# CNEPuckRevG_Drivers_2.net
KiCad netlist of a schematic drawn in Altium Designer
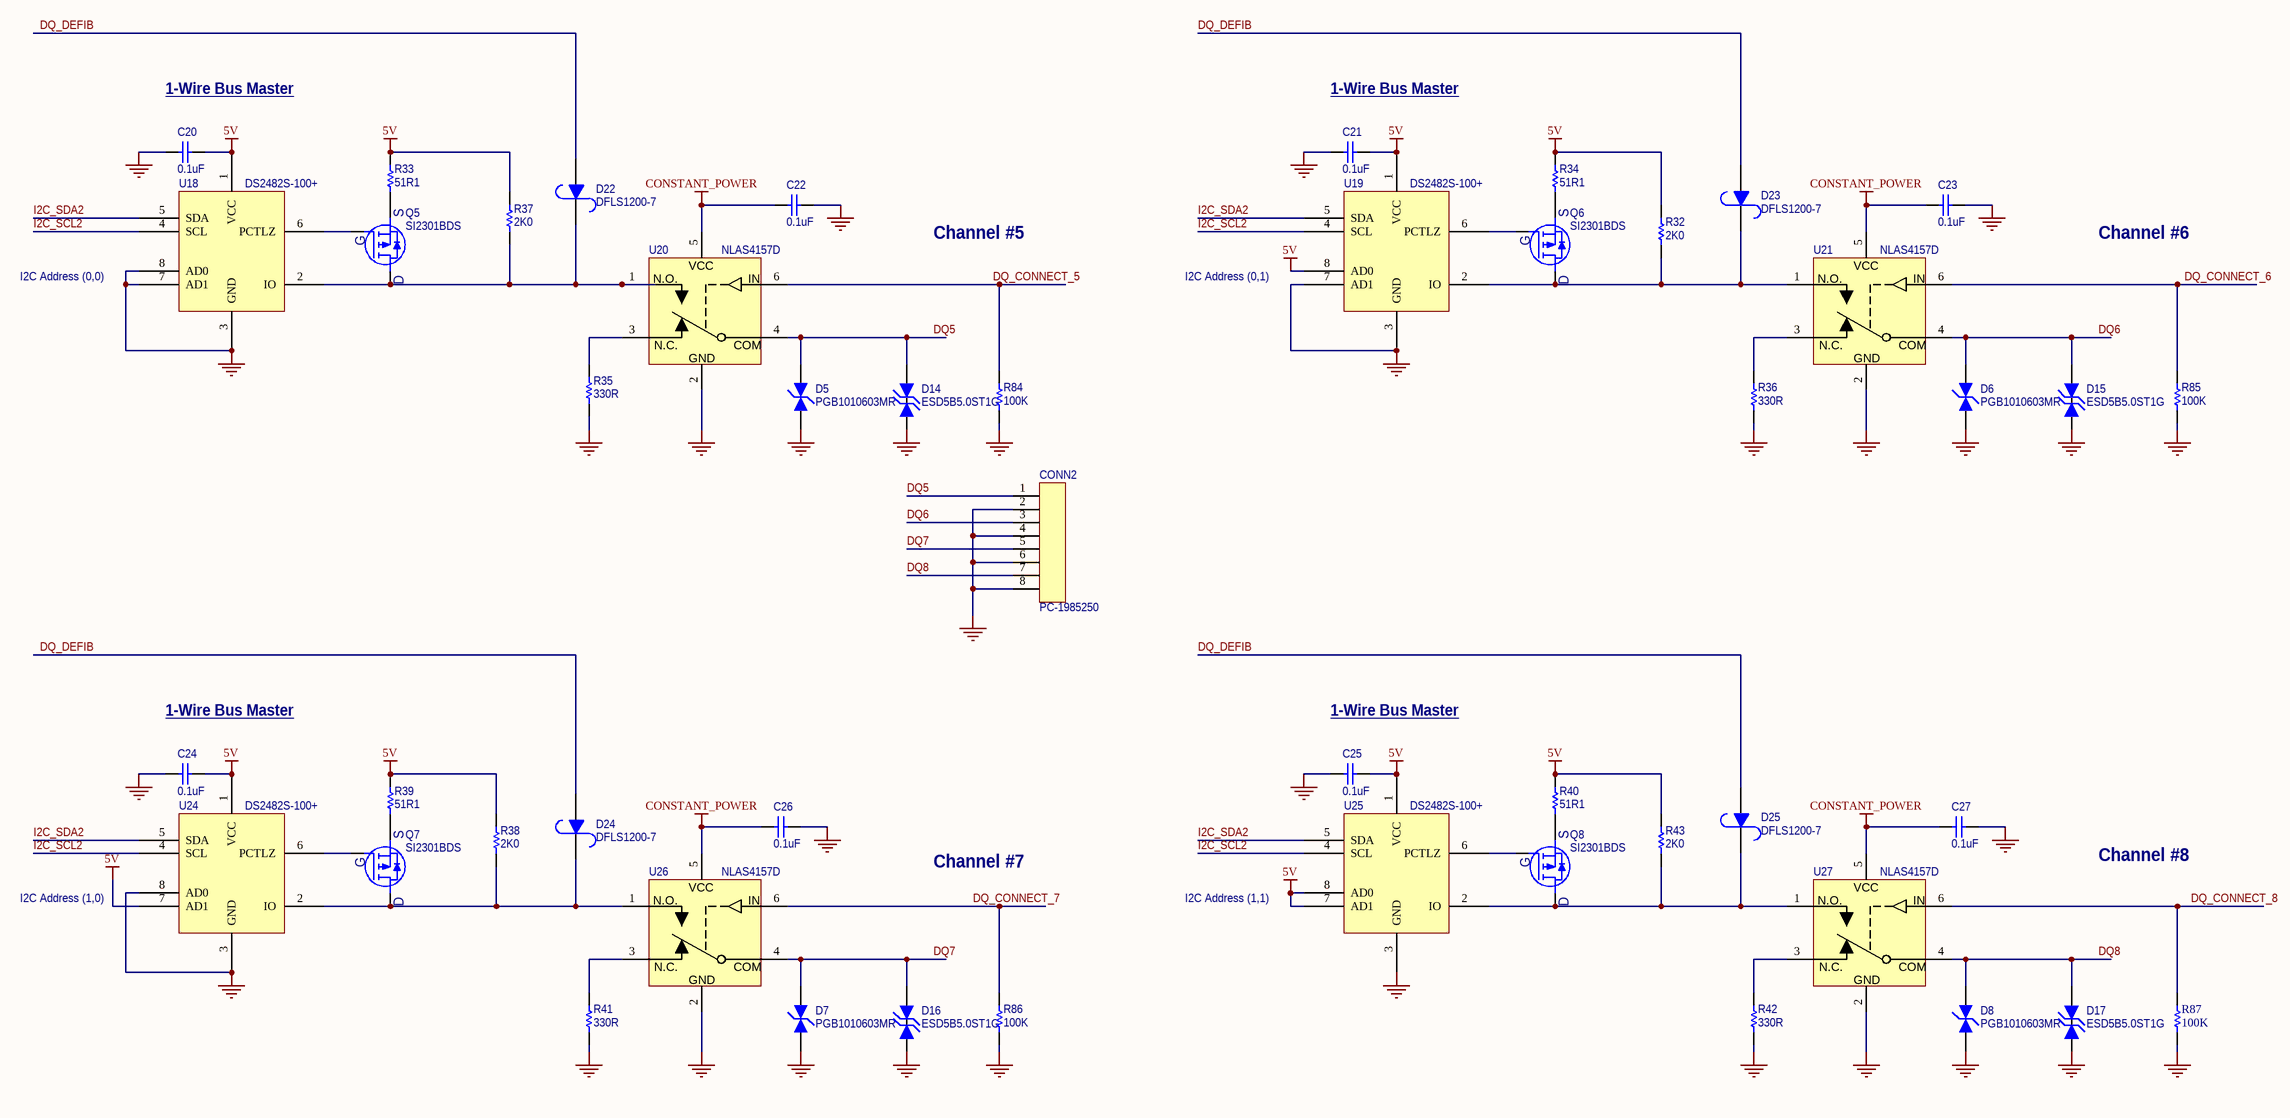
[diagram p0: CNEPuckRevG_Drivers_2.SchDoc]

(export (version "E")
  (design (tool "Eeschema 10.0.6"))
  (components
    (comp (ref "C20")
      (value "0.1uF")
      (footprint "RC0603")
      (description "CAP CERM .1UF 10% 16V X7R 0603")
      (fields (field (name "TOLERANCE") "±10%") (field (name "MANUFACTURER PART NUMBER") "0603YC104KAT2A"))
      (libsource (lib "Swage") (part "0603YC104KAT2A"))
    )
    (comp (ref "C21")
      (value "0.1uF")
      (footprint "RC0603")
      (description "CAP CERM .1UF 10% 16V X7R 0603")
      (fields (field (name "TOLERANCE") "±10%") (field (name "MANUFACTURER PART NUMBER") "0603YC104KAT2A"))
      (libsource (lib "Swage") (part "0603YC104KAT2A"))
    )
    (comp (ref "C22")
      (value "0.1uF")
      (footprint "RC0603")
      (description "CAP CERM .1UF 10% 16V X7R 0603")
      (fields (field (name "TOLERANCE") "±10%") (field (name "MANUFACTURER PART NUMBER") "0603YC104KAT2A"))
      (libsource (lib "Swage") (part "0603YC104KAT2A"))
    )
    (comp (ref "C23")
      (value "0.1uF")
      (footprint "RC0603")
      (description "CAP CERM .1UF 10% 16V X7R 0603")
      (fields (field (name "TOLERANCE") "±10%") (field (name "MANUFACTURER PART NUMBER") "0603YC104KAT2A"))
      (libsource (lib "Swage") (part "0603YC104KAT2A"))
    )
    (comp (ref "C24")
      (value "0.1uF")
      (footprint "RC0603")
      (description "CAP CERM .1UF 10% 16V X7R 0603")
      (fields (field (name "TOLERANCE") "±10%") (field (name "MANUFACTURER PART NUMBER") "0603YC104KAT2A"))
      (libsource (lib "Swage") (part "0603YC104KAT2A"))
    )
    (comp (ref "C25")
      (value "0.1uF")
      (footprint "RC0603")
      (description "CAP CERM .1UF 10% 16V X7R 0603")
      (fields (field (name "TOLERANCE") "±10%") (field (name "MANUFACTURER PART NUMBER") "0603YC104KAT2A"))
      (libsource (lib "Swage") (part "0603YC104KAT2A"))
    )
    (comp (ref "C26")
      (value "0.1uF")
      (footprint "RC0603")
      (description "CAP CERM .1UF 10% 16V X7R 0603")
      (fields (field (name "TOLERANCE") "±10%") (field (name "MANUFACTURER PART NUMBER") "0603YC104KAT2A"))
      (libsource (lib "Swage") (part "0603YC104KAT2A"))
    )
    (comp (ref "C27")
      (value "0.1uF")
      (footprint "RC0603")
      (description "CAP CERM .1UF 10% 16V X7R 0603")
      (fields (field (name "TOLERANCE") "±10%") (field (name "MANUFACTURER PART NUMBER") "0603YC104KAT2A"))
      (libsource (lib "Swage") (part "0603YC104KAT2A"))
    )
    (comp (ref "CONN2")
      (value "PC-1985250")
      (footprint "PTSA1.5/8-3.5-Z")
      (description "TERM BLOCK PCB 8POS 3.5MM GREEN")
      (fields
        (field (name "MANUFACTURER") "Phoenix Contact")
        (field (name "MANUFACTURER PART NUMBER") "1985250")
      )
      (libsource (lib "Swage") (part "1985250"))
    )
    (comp (ref "D5")
      (value "PGB1010603MR")
      (footprint "RC0603")
      (description "SUPPRESSOR ESD 24VDC 0603 SMD")
      (fields (field (name "MANUFACTURER") "Littelfuse Inc"))
      (libsource (lib "Swage") (part "PGB1010603MR"))
    )
    (comp (ref "D6")
      (value "PGB1010603MR")
      (footprint "RC0603")
      (description "SUPPRESSOR ESD 24VDC 0603 SMD")
      (fields (field (name "MANUFACTURER") "Littelfuse Inc"))
      (libsource (lib "Swage") (part "PGB1010603MR"))
    )
    (comp (ref "D7")
      (value "PGB1010603MR")
      (footprint "RC0603")
      (description "SUPPRESSOR ESD 24VDC 0603 SMD")
      (fields (field (name "MANUFACTURER") "Littelfuse Inc"))
      (libsource (lib "Swage") (part "PGB1010603MR"))
    )
    (comp (ref "D8")
      (value "PGB1010603MR")
      (footprint "RC0603")
      (description "SUPPRESSOR ESD 24VDC 0603 SMD")
      (fields (field (name "MANUFACTURER") "Littelfuse Inc"))
      (libsource (lib "Swage") (part "PGB1010603MR"))
    )
    (comp (ref "D14")
      (value "ESD5B5.0ST1G")
      (footprint "SOD-523")
      (description "TVS BIDIRECT 50W SOD523")
      (fields (field (name "MANUFACTURER") "ON Semiconductor"))
      (libsource (lib "Swage") (part "ESD5B5.0ST1G"))
    )
    (comp (ref "D15")
      (value "ESD5B5.0ST1G")
      (footprint "SOD-523")
      (description "TVS BIDIRECT 50W SOD523")
      (fields (field (name "MANUFACTURER") "ON Semiconductor"))
      (libsource (lib "Swage") (part "ESD5B5.0ST1G"))
    )
    (comp (ref "D16")
      (value "ESD5B5.0ST1G")
      (footprint "SOD-523")
      (description "TVS BIDIRECT 50W SOD523")
      (fields (field (name "MANUFACTURER") "ON Semiconductor"))
      (libsource (lib "Swage") (part "ESD5B5.0ST1G"))
    )
    (comp (ref "D17")
      (value "ESD5B5.0ST1G")
      (footprint "SOD-523")
      (description "TVS BIDIRECT 50W SOD523")
      (fields (field (name "MANUFACTURER") "ON Semiconductor"))
      (libsource (lib "Swage") (part "ESD5B5.0ST1G"))
    )
    (comp (ref "D22")
      (value "DFLS1200-7")
      (footprint "POWERDI-123")
      (description "DIODE SCHOTTKY 1A 200V PWRDI 123")
      (fields (field (name "MANUFACTURER") "Diodes Inc"))
      (libsource (lib "Swage") (part "DFLS1200-7"))
    )
    (comp (ref "D23")
      (value "DFLS1200-7")
      (footprint "POWERDI-123")
      (description "DIODE SCHOTTKY 1A 200V PWRDI 123")
      (fields (field (name "MANUFACTURER") "Diodes Inc"))
      (libsource (lib "Swage") (part "DFLS1200-7"))
    )
    (comp (ref "D24")
      (value "DFLS1200-7")
      (footprint "POWERDI-123")
      (description "DIODE SCHOTTKY 1A 200V PWRDI 123")
      (fields (field (name "MANUFACTURER") "Diodes Inc"))
      (libsource (lib "Swage") (part "DFLS1200-7"))
    )
    (comp (ref "D25")
      (value "DFLS1200-7")
      (footprint "POWERDI-123")
      (description "DIODE SCHOTTKY 1A 200V PWRDI 123")
      (fields (field (name "MANUFACTURER") "Diodes Inc"))
      (libsource (lib "Swage") (part "DFLS1200-7"))
    )
    (comp (ref "Q5")
      (value "SI2301BDS")
      (footprint "SOT23(DGS)")
      (description "MOSFET P-CH 20V 2.2A SOT23-3")
      (fields
        (field (name "MANUFACTURER") "Vishay/Siliconix")
        (field (name "MANUFACTURER PART NUMBER") "SI2301BDS-T1-E3")
      )
      (libsource (lib "Swage") (part "SI2301BDS-T1-E3"))
    )
    (comp (ref "Q6")
      (value "SI2301BDS")
      (footprint "SOT23(DGS)")
      (description "MOSFET P-CH 20V 2.2A SOT23-3")
      (fields
        (field (name "MANUFACTURER") "Vishay/Siliconix")
        (field (name "MANUFACTURER PART NUMBER") "SI2301BDS-T1-E3")
      )
      (libsource (lib "Swage") (part "SI2301BDS-T1-E3"))
    )
    (comp (ref "Q7")
      (value "SI2301BDS")
      (footprint "SOT23(DGS)")
      (description "MOSFET P-CH 20V 2.2A SOT23-3")
      (fields
        (field (name "MANUFACTURER") "Vishay/Siliconix")
        (field (name "MANUFACTURER PART NUMBER") "SI2301BDS-T1-E3")
      )
      (libsource (lib "Swage") (part "SI2301BDS-T1-E3"))
    )
    (comp (ref "Q8")
      (value "SI2301BDS")
      (footprint "SOT23(DGS)")
      (description "MOSFET P-CH 20V 2.2A SOT23-3")
      (fields
        (field (name "MANUFACTURER") "Vishay/Siliconix")
        (field (name "MANUFACTURER PART NUMBER") "SI2301BDS-T1-E3")
      )
      (libsource (lib "Swage") (part "SI2301BDS-T1-E3"))
    )
    (comp (ref "R32")
      (value "2K0")
      (footprint "RC0603")
      (description "RES 2K OHM 1/10W 1% 0603 SMD")
      (fields
        (field (name "MANUFACTURER") "Panasonic Electronic Components")
        (field (name "MANUFACTURER PART NUMBER") "ERJ-3EKF2001V")
      )
      (libsource (lib "Swage") (part "ERJ-3EKF2001V"))
    )
    (comp (ref "R33")
      (value "51R1")
      (footprint "RC0603")
      (description "RES 51.1 OHM .25W 1% 0603 SMD")
      (fields
        (field (name "MANUFACTURER") "Vishay Dale")
        (field (name "MANUFACTURER PART NUMBER") "CRCW060351R1FKEAHP")
      )
      (libsource (lib "Swage") (part "CRCW060351R1FKEAHP"))
    )
    (comp (ref "R34")
      (value "51R1")
      (footprint "RC0603")
      (description "RES 51.1 OHM .25W 1% 0603 SMD")
      (fields
        (field (name "MANUFACTURER") "Vishay Dale")
        (field (name "MANUFACTURER PART NUMBER") "CRCW060351R1FKEAHP")
      )
      (libsource (lib "Swage") (part "CRCW060351R1FKEAHP"))
    )
    (comp (ref "R35")
      (value "330R")
      (footprint "RC0805")
      (description "RES 330 OHM 1/8W 5% 0805 SMD")
      (fields
        (field (name "MANUFACTURER") "KOA Speer Technologies")
        (field (name "MANUFACTURER PART NUMBER") "RK73B2ATTD331J")
      )
      (libsource (lib "Swage") (part "ERJ-6GEYJ331V"))
    )
    (comp (ref "R36")
      (value "330R")
      (footprint "RC0805")
      (description "RES 330 OHM 1/8W 5% 0805 SMD")
      (fields
        (field (name "MANUFACTURER") "KOA Speer Technologies")
        (field (name "MANUFACTURER PART NUMBER") "RK73B2ATTD331J")
      )
      (libsource (lib "Swage") (part "ERJ-6GEYJ331V"))
    )
    (comp (ref "R37")
      (value "2K0")
      (footprint "RC0603")
      (description "RES 2K OHM 1/10W 1% 0603 SMD")
      (fields
        (field (name "MANUFACTURER") "Panasonic Electronic Components")
        (field (name "MANUFACTURER PART NUMBER") "ERJ-3EKF2001V")
      )
      (libsource (lib "Swage") (part "ERJ-3EKF2001V"))
    )
    (comp (ref "R38")
      (value "2K0")
      (footprint "RC0603")
      (description "RES 2K OHM 1/10W 1% 0603 SMD")
      (fields
        (field (name "MANUFACTURER") "Panasonic Electronic Components")
        (field (name "MANUFACTURER PART NUMBER") "ERJ-3EKF2001V")
      )
      (libsource (lib "Swage") (part "ERJ-3EKF2001V"))
    )
    (comp (ref "R39")
      (value "51R1")
      (footprint "RC0603")
      (description "RES 51.1 OHM .25W 1% 0603 SMD")
      (fields
        (field (name "MANUFACTURER") "Vishay Dale")
        (field (name "MANUFACTURER PART NUMBER") "CRCW060351R1FKEAHP")
      )
      (libsource (lib "Swage") (part "CRCW060351R1FKEAHP"))
    )
    (comp (ref "R40")
      (value "51R1")
      (footprint "RC0603")
      (description "RES 51.1 OHM .25W 1% 0603 SMD")
      (fields
        (field (name "MANUFACTURER") "Vishay Dale")
        (field (name "MANUFACTURER PART NUMBER") "CRCW060351R1FKEAHP")
      )
      (libsource (lib "Swage") (part "CRCW060351R1FKEAHP"))
    )
    (comp (ref "R41")
      (value "330R")
      (footprint "RC0805")
      (description "RES 330 OHM 1/8W 5% 0805 SMD")
      (fields
        (field (name "MANUFACTURER") "KOA Speer Technologies")
        (field (name "MANUFACTURER PART NUMBER") "RK73B2ATTD331J")
      )
      (libsource (lib "Swage") (part "ERJ-6GEYJ331V"))
    )
    (comp (ref "R42")
      (value "330R")
      (footprint "RC0805")
      (description "RES 330 OHM 1/8W 5% 0805 SMD")
      (fields
        (field (name "MANUFACTURER") "KOA Speer Technologies")
        (field (name "MANUFACTURER PART NUMBER") "RK73B2ATTD331J")
      )
      (libsource (lib "Swage") (part "ERJ-6GEYJ331V"))
    )
    (comp (ref "R43")
      (value "2K0")
      (footprint "RC0603")
      (description "RES 2K OHM 1/10W 1% 0603 SMD")
      (fields
        (field (name "MANUFACTURER") "Panasonic Electronic Components")
        (field (name "MANUFACTURER PART NUMBER") "ERJ-3EKF2001V")
      )
      (libsource (lib "Swage") (part "ERJ-3EKF2001V"))
    )
    (comp (ref "R84")
      (value "100K")
      (footprint "RC0603")
      (description "RES 100K OHM 1/10W 5% 0603 SMD")
      (fields
        (field (name "MANUFACTURER") "Panasonic Electronic Components")
        (field (name "MANUFACTURER PART NUMBER") "ERJ-3GEYJ104V")
      )
      (libsource (lib "Swage") (part "ERJ-3GEYJ104V"))
    )
    (comp (ref "R85")
      (value "100K")
      (footprint "RC0603")
      (description "RES 100K OHM 1/10W 5% 0603 SMD")
      (fields
        (field (name "MANUFACTURER") "Panasonic Electronic Components")
        (field (name "MANUFACTURER PART NUMBER") "ERJ-3GEYJ104V")
      )
      (libsource (lib "Swage") (part "ERJ-3GEYJ104V"))
    )
    (comp (ref "R86")
      (value "100K")
      (footprint "RC0603")
      (description "RES 100K OHM 1/10W 5% 0603 SMD")
      (fields
        (field (name "MANUFACTURER") "Panasonic Electronic Components")
        (field (name "MANUFACTURER PART NUMBER") "ERJ-3GEYJ104V")
      )
      (libsource (lib "Swage") (part "ERJ-3GEYJ104V"))
    )
    (comp (ref "R87")
      (value "100K")
      (footprint "RC0603")
      (description "RES 100K OHM 1/10W 5% 0603 SMD")
      (fields
        (field (name "MANUFACTURER") "Panasonic Electronic Components")
        (field (name "MANUFACTURER PART NUMBER") "ERJ-3GEYJ104V")
      )
      (libsource (lib "Swage") (part "ERJ-3GEYJ104V"))
    )
    (comp (ref "U18")
      (value "DS2482S-100+")
      (footprint "SOIC127P580X153-8N")
      (description "IC BRIDGE I2C TO 1-WIRE 8-SOIC")
      (fields (field (name "MANUFACTURER") "Maxim Integrated"))
      (libsource (lib "Swage") (part "DS2482S-100+"))
    )
    (comp (ref "U19")
      (value "DS2482S-100+")
      (footprint "SOIC127P580X153-8N")
      (description "IC BRIDGE I2C TO 1-WIRE 8-SOIC")
      (fields (field (name "MANUFACTURER") "Maxim Integrated"))
      (libsource (lib "Swage") (part "DS2482S-100+"))
    )
    (comp (ref "U20")
      (value "NLAS4157D")
      (footprint "TS5A3160")
      (description "IC SWITCH SPDT SC88")
      (fields
        (field (name "MANUFACTURER") "ON Semiconductor")
        (field (name "MANUFACTURER PART NUMBER") "NLAS4157DFT2G")
      )
      (libsource (lib "Swage") (part "NLAS4157DFT2G"))
    )
    (comp (ref "U21")
      (value "NLAS4157D")
      (footprint "TS5A3160")
      (description "IC SWITCH SPDT SC88")
      (fields
        (field (name "MANUFACTURER") "ON Semiconductor")
        (field (name "MANUFACTURER PART NUMBER") "NLAS4157DFT2G")
      )
      (libsource (lib "Swage") (part "NLAS4157DFT2G"))
    )
    (comp (ref "U24")
      (value "DS2482S-100+")
      (footprint "SOIC127P580X153-8N")
      (description "IC BRIDGE I2C TO 1-WIRE 8-SOIC")
      (fields (field (name "MANUFACTURER") "Maxim Integrated"))
      (libsource (lib "Swage") (part "DS2482S-100+"))
    )
    (comp (ref "U25")
      (value "DS2482S-100+")
      (footprint "SOIC127P580X153-8N")
      (description "IC BRIDGE I2C TO 1-WIRE 8-SOIC")
      (fields (field (name "MANUFACTURER") "Maxim Integrated"))
      (libsource (lib "Swage") (part "DS2482S-100+"))
    )
    (comp (ref "U26")
      (value "NLAS4157D")
      (footprint "TS5A3160")
      (description "IC SWITCH SPDT SC88")
      (fields
        (field (name "MANUFACTURER") "ON Semiconductor")
        (field (name "MANUFACTURER PART NUMBER") "NLAS4157DFT2G")
      )
      (libsource (lib "Swage") (part "NLAS4157DFT2G"))
    )
    (comp (ref "U27")
      (value "NLAS4157D")
      (footprint "TS5A3160")
      (description "IC SWITCH SPDT SC88")
      (fields
        (field (name "MANUFACTURER") "ON Semiconductor")
        (field (name "MANUFACTURER PART NUMBER") "NLAS4157DFT2G")
      )
      (libsource (lib "Swage") (part "NLAS4157DFT2G"))
    )
  )
  (nets
    (net (code "1") (name "/DQ5") (class "Default")
      (node (ref "CONN2") (pin "1") (pinfunction "1_1") (pintype "passive"))
      (node (ref "D14") (pin "2") (pinfunction "2_2") (pintype "passive"))
      (node (ref "D5") (pin "2") (pinfunction "2_2") (pintype "passive"))
      (node (ref "U20") (pin "4") (pinfunction "4_4") (pintype "passive"))
    )
    (net (code "2") (name "/DQ6") (class "Default")
      (node (ref "CONN2") (pin "3") (pinfunction "3_3") (pintype "passive"))
      (node (ref "D15") (pin "2") (pinfunction "2_2") (pintype "passive"))
      (node (ref "D6") (pin "2") (pinfunction "2_2") (pintype "passive"))
      (node (ref "U21") (pin "4") (pinfunction "4_4") (pintype "passive"))
    )
    (net (code "3") (name "/DQ7") (class "Default")
      (node (ref "CONN2") (pin "5") (pinfunction "5_5") (pintype "passive"))
      (node (ref "D16") (pin "2") (pinfunction "2_2") (pintype "passive"))
      (node (ref "D7") (pin "2") (pinfunction "2_2") (pintype "passive"))
      (node (ref "U26") (pin "4") (pinfunction "4_4") (pintype "passive"))
    )
    (net (code "4") (name "/DQ8") (class "Default")
      (node (ref "CONN2") (pin "7") (pinfunction "7_7") (pintype "passive"))
      (node (ref "D17") (pin "2") (pinfunction "2_2") (pintype "passive"))
      (node (ref "D8") (pin "2") (pinfunction "2_2") (pintype "passive"))
      (node (ref "U27") (pin "4") (pinfunction "4_4") (pintype "passive"))
    )
    (net (code "5") (name "/DQ_CONNECT_5") (class "Default")
      (node (ref "R84") (pin "1") (pinfunction "1_1") (pintype "passive"))
      (node (ref "U20") (pin "6") (pinfunction "6_6") (pintype "passive"))
    )
    (net (code "6") (name "/DQ_CONNECT_6") (class "Default")
      (node (ref "R85") (pin "1") (pinfunction "1_1") (pintype "passive"))
      (node (ref "U21") (pin "6") (pinfunction "6_6") (pintype "passive"))
    )
    (net (code "7") (name "/DQ_CONNECT_7") (class "Default")
      (node (ref "R86") (pin "1") (pinfunction "1_1") (pintype "passive"))
      (node (ref "U26") (pin "6") (pinfunction "6_6") (pintype "passive"))
    )
    (net (code "8") (name "/DQ_CONNECT_8") (class "Default")
      (node (ref "R87") (pin "1") (pinfunction "1_1") (pintype "passive"))
      (node (ref "U27") (pin "6") (pinfunction "6_6") (pintype "passive"))
    )
    (net (code "9") (name "/DQ_DEFIB") (class "Default")
      (node (ref "D22") (pin "1") (pinfunction "A_1") (pintype "passive"))
      (node (ref "D23") (pin "1") (pinfunction "A_1") (pintype "passive"))
      (node (ref "D24") (pin "1") (pinfunction "A_1") (pintype "passive"))
      (node (ref "D25") (pin "1") (pinfunction "A_1") (pintype "passive"))
    )
    (net (code "10") (name "/I2C_SCL2") (class "Default")
      (node (ref "U18") (pin "4") (pinfunction "SCL_4") (pintype "passive"))
      (node (ref "U19") (pin "4") (pinfunction "SCL_4") (pintype "passive"))
      (node (ref "U24") (pin "4") (pinfunction "SCL_4") (pintype "passive"))
      (node (ref "U25") (pin "4") (pinfunction "SCL_4") (pintype "passive"))
    )
    (net (code "11") (name "/I2C_SDA2") (class "Default")
      (node (ref "U18") (pin "5") (pinfunction "SDA_5") (pintype "passive"))
      (node (ref "U19") (pin "5") (pinfunction "SDA_5") (pintype "passive"))
      (node (ref "U24") (pin "5") (pinfunction "SDA_5") (pintype "passive"))
      (node (ref "U25") (pin "5") (pinfunction "SDA_5") (pintype "passive"))
    )
    (net (code "12") (name "5V") (class "Default")
      (node (ref "C20") (pin "2") (pinfunction "2_2") (pintype "passive"))
      (node (ref "C21") (pin "2") (pinfunction "2_2") (pintype "passive"))
      (node (ref "C24") (pin "2") (pinfunction "2_2") (pintype "passive"))
      (node (ref "C25") (pin "2") (pinfunction "2_2") (pintype "passive"))
      (node (ref "R32") (pin "1") (pinfunction "1_1") (pintype "passive"))
      (node (ref "R33") (pin "1") (pinfunction "1_1") (pintype "passive"))
      (node (ref "R34") (pin "1") (pinfunction "1_1") (pintype "passive"))
      (node (ref "R37") (pin "1") (pinfunction "1_1") (pintype "passive"))
      (node (ref "R38") (pin "1") (pinfunction "1_1") (pintype "passive"))
      (node (ref "R39") (pin "1") (pinfunction "1_1") (pintype "passive"))
      (node (ref "R40") (pin "1") (pinfunction "1_1") (pintype "passive"))
      (node (ref "R43") (pin "1") (pinfunction "1_1") (pintype "passive"))
      (node (ref "U18") (pin "1") (pinfunction "VCC_1") (pintype "passive"))
      (node (ref "U19") (pin "1") (pinfunction "VCC_1") (pintype "passive"))
      (node (ref "U19") (pin "8") (pinfunction "AD0_8") (pintype "passive"))
      (node (ref "U24") (pin "1") (pinfunction "VCC_1") (pintype "passive"))
      (node (ref "U24") (pin "7") (pinfunction "AD1_7") (pintype "passive"))
      (node (ref "U25") (pin "1") (pinfunction "VCC_1") (pintype "passive"))
      (node (ref "U25") (pin "7") (pinfunction "AD1_7") (pintype "passive"))
      (node (ref "U25") (pin "8") (pinfunction "AD0_8") (pintype "passive"))
    )
    (net (code "13") (name "CONSTANT_POWER") (class "Default")
      (node (ref "C22") (pin "1") (pinfunction "1_1") (pintype "passive"))
      (node (ref "C23") (pin "1") (pinfunction "1_1") (pintype "passive"))
      (node (ref "C26") (pin "1") (pinfunction "1_1") (pintype "passive"))
      (node (ref "C27") (pin "1") (pinfunction "1_1") (pintype "passive"))
      (node (ref "U20") (pin "5") (pinfunction "5_5") (pintype "passive"))
      (node (ref "U21") (pin "5") (pinfunction "5_5") (pintype "passive"))
      (node (ref "U26") (pin "5") (pinfunction "5_5") (pintype "passive"))
      (node (ref "U27") (pin "5") (pinfunction "5_5") (pintype "passive"))
    )
    (net (code "14") (name "GND") (class "Default")
      (node (ref "C20") (pin "1") (pinfunction "1_1") (pintype "passive"))
      (node (ref "C21") (pin "1") (pinfunction "1_1") (pintype "passive"))
      (node (ref "C22") (pin "2") (pinfunction "2_2") (pintype "passive"))
      (node (ref "C23") (pin "2") (pinfunction "2_2") (pintype "passive"))
      (node (ref "C24") (pin "1") (pinfunction "1_1") (pintype "passive"))
      (node (ref "C25") (pin "1") (pinfunction "1_1") (pintype "passive"))
      (node (ref "C26") (pin "2") (pinfunction "2_2") (pintype "passive"))
      (node (ref "C27") (pin "2") (pinfunction "2_2") (pintype "passive"))
      (node (ref "CONN2") (pin "2") (pinfunction "2_2") (pintype "passive"))
      (node (ref "CONN2") (pin "4") (pinfunction "4_4") (pintype "passive"))
      (node (ref "CONN2") (pin "6") (pinfunction "6_6") (pintype "passive"))
      (node (ref "CONN2") (pin "8") (pinfunction "8_8") (pintype "passive"))
      (node (ref "D14") (pin "1") (pintype "passive"))
      (node (ref "D15") (pin "1") (pintype "passive"))
      (node (ref "D16") (pin "1") (pintype "passive"))
      (node (ref "D17") (pin "1") (pintype "passive"))
      (node (ref "D5") (pin "1") (pintype "passive"))
      (node (ref "D6") (pin "1") (pintype "passive"))
      (node (ref "D7") (pin "1") (pintype "passive"))
      (node (ref "D8") (pin "1") (pintype "passive"))
      (node (ref "R35") (pin "2") (pinfunction "2_2") (pintype "passive"))
      (node (ref "R36") (pin "1") (pinfunction "1_1") (pintype "passive"))
      (node (ref "R41") (pin "2") (pinfunction "2_2") (pintype "passive"))
      (node (ref "R42") (pin "2") (pinfunction "2_2") (pintype "passive"))
      (node (ref "R84") (pin "2") (pinfunction "2_2") (pintype "passive"))
      (node (ref "R85") (pin "2") (pinfunction "2_2") (pintype "passive"))
      (node (ref "R86") (pin "2") (pinfunction "2_2") (pintype "passive"))
      (node (ref "R87") (pin "2") (pinfunction "2_2") (pintype "passive"))
      (node (ref "U18") (pin "3") (pinfunction "GND_3") (pintype "passive"))
      (node (ref "U18") (pin "7") (pinfunction "AD1_7") (pintype "passive"))
      (node (ref "U18") (pin "8") (pinfunction "AD0_8") (pintype "passive"))
      (node (ref "U19") (pin "3") (pinfunction "GND_3") (pintype "passive"))
      (node (ref "U19") (pin "7") (pinfunction "AD1_7") (pintype "passive"))
      (node (ref "U20") (pin "2") (pinfunction "GND_2") (pintype "passive"))
      (node (ref "U21") (pin "2") (pinfunction "GND_2") (pintype "passive"))
      (node (ref "U24") (pin "3") (pinfunction "GND_3") (pintype "passive"))
      (node (ref "U24") (pin "8") (pinfunction "AD0_8") (pintype "passive"))
      (node (ref "U25") (pin "3") (pinfunction "GND_3") (pintype "passive"))
      (node (ref "U26") (pin "2") (pinfunction "GND_2") (pintype "passive"))
      (node (ref "U27") (pin "2") (pinfunction "GND_2") (pintype "passive"))
    )
    (net (code "15") (name "Net-(D22-K)") (class "Default")
      (node (ref "D22") (pin "2") (pinfunction "K_2") (pintype "passive"))
      (node (ref "Q5") (pin "D") (pinfunction "D_D") (pintype "passive"))
      (node (ref "R37") (pin "2") (pinfunction "2_2") (pintype "passive"))
      (node (ref "U18") (pin "2") (pinfunction "IO_2") (pintype "passive"))
      (node (ref "U20") (pin "1") (pinfunction "NO_1") (pintype "passive"))
    )
    (net (code "16") (name "Net-(D23-K)") (class "Default")
      (node (ref "D23") (pin "2") (pinfunction "K_2") (pintype "passive"))
      (node (ref "Q6") (pin "D") (pinfunction "D_D") (pintype "passive"))
      (node (ref "R32") (pin "2") (pinfunction "2_2") (pintype "passive"))
      (node (ref "U19") (pin "2") (pinfunction "IO_2") (pintype "passive"))
      (node (ref "U21") (pin "1") (pinfunction "NO_1") (pintype "passive"))
    )
    (net (code "17") (name "Net-(D24-K)") (class "Default")
      (node (ref "D24") (pin "2") (pinfunction "K_2") (pintype "passive"))
      (node (ref "Q7") (pin "D") (pinfunction "D_D") (pintype "passive"))
      (node (ref "R38") (pin "2") (pinfunction "2_2") (pintype "passive"))
      (node (ref "U24") (pin "2") (pinfunction "IO_2") (pintype "passive"))
      (node (ref "U26") (pin "1") (pinfunction "NO_1") (pintype "passive"))
    )
    (net (code "18") (name "Net-(D25-K)") (class "Default")
      (node (ref "D25") (pin "2") (pinfunction "K_2") (pintype "passive"))
      (node (ref "Q8") (pin "D") (pinfunction "D_D") (pintype "passive"))
      (node (ref "R43") (pin "2") (pinfunction "2_2") (pintype "passive"))
      (node (ref "U25") (pin "2") (pinfunction "IO_2") (pintype "passive"))
      (node (ref "U27") (pin "1") (pinfunction "NO_1") (pintype "passive"))
    )
    (net (code "19") (name "Net-(Q5-PadS)") (class "Default")
      (node (ref "Q5") (pin "S") (pinfunction "S_S") (pintype "passive"))
      (node (ref "R33") (pin "2") (pinfunction "2_2") (pintype "passive"))
    )
    (net (code "20") (name "Net-(Q6-PadS)") (class "Default")
      (node (ref "Q6") (pin "S") (pinfunction "S_S") (pintype "passive"))
      (node (ref "R34") (pin "2") (pinfunction "2_2") (pintype "passive"))
    )
    (net (code "21") (name "Net-(Q7-PadS)") (class "Default")
      (node (ref "Q7") (pin "S") (pinfunction "S_S") (pintype "passive"))
      (node (ref "R39") (pin "2") (pinfunction "2_2") (pintype "passive"))
    )
    (net (code "22") (name "Net-(Q8-PadS)") (class "Default")
      (node (ref "Q8") (pin "S") (pinfunction "S_S") (pintype "passive"))
      (node (ref "R40") (pin "2") (pinfunction "2_2") (pintype "passive"))
    )
    (net (code "23") (name "Net-(U18-PCTLZ)") (class "Default")
      (node (ref "Q5") (pin "G") (pinfunction "G_G") (pintype "passive"))
      (node (ref "U18") (pin "6") (pinfunction "PCTLZ_6") (pintype "passive"))
    )
    (net (code "24") (name "Net-(U19-PCTLZ)") (class "Default")
      (node (ref "Q6") (pin "G") (pinfunction "G_G") (pintype "passive"))
      (node (ref "U19") (pin "6") (pinfunction "PCTLZ_6") (pintype "passive"))
    )
    (net (code "25") (name "Net-(U20-NC)") (class "Default")
      (node (ref "R35") (pin "1") (pinfunction "1_1") (pintype "passive"))
      (node (ref "U20") (pin "3") (pinfunction "NC_3") (pintype "passive"))
    )
    (net (code "26") (name "Net-(U21-NC)") (class "Default")
      (node (ref "R36") (pin "2") (pinfunction "2_2") (pintype "passive"))
      (node (ref "U21") (pin "3") (pinfunction "NC_3") (pintype "passive"))
    )
    (net (code "27") (name "Net-(U24-PCTLZ)") (class "Default")
      (node (ref "Q7") (pin "G") (pinfunction "G_G") (pintype "passive"))
      (node (ref "U24") (pin "6") (pinfunction "PCTLZ_6") (pintype "passive"))
    )
    (net (code "28") (name "Net-(U25-PCTLZ)") (class "Default")
      (node (ref "Q8") (pin "G") (pinfunction "G_G") (pintype "passive"))
      (node (ref "U25") (pin "6") (pinfunction "PCTLZ_6") (pintype "passive"))
    )
    (net (code "29") (name "Net-(U26-NC)") (class "Default")
      (node (ref "R41") (pin "1") (pinfunction "1_1") (pintype "passive"))
      (node (ref "U26") (pin "3") (pinfunction "NC_3") (pintype "passive"))
    )
    (net (code "30") (name "Net-(U27-NC)") (class "Default")
      (node (ref "R42") (pin "1") (pinfunction "1_1") (pintype "passive"))
      (node (ref "U27") (pin "3") (pinfunction "NC_3") (pintype "passive"))
    )
  )
)
